# Revolution.net
KiCad netlist of a schematic drawn in Altium Designer
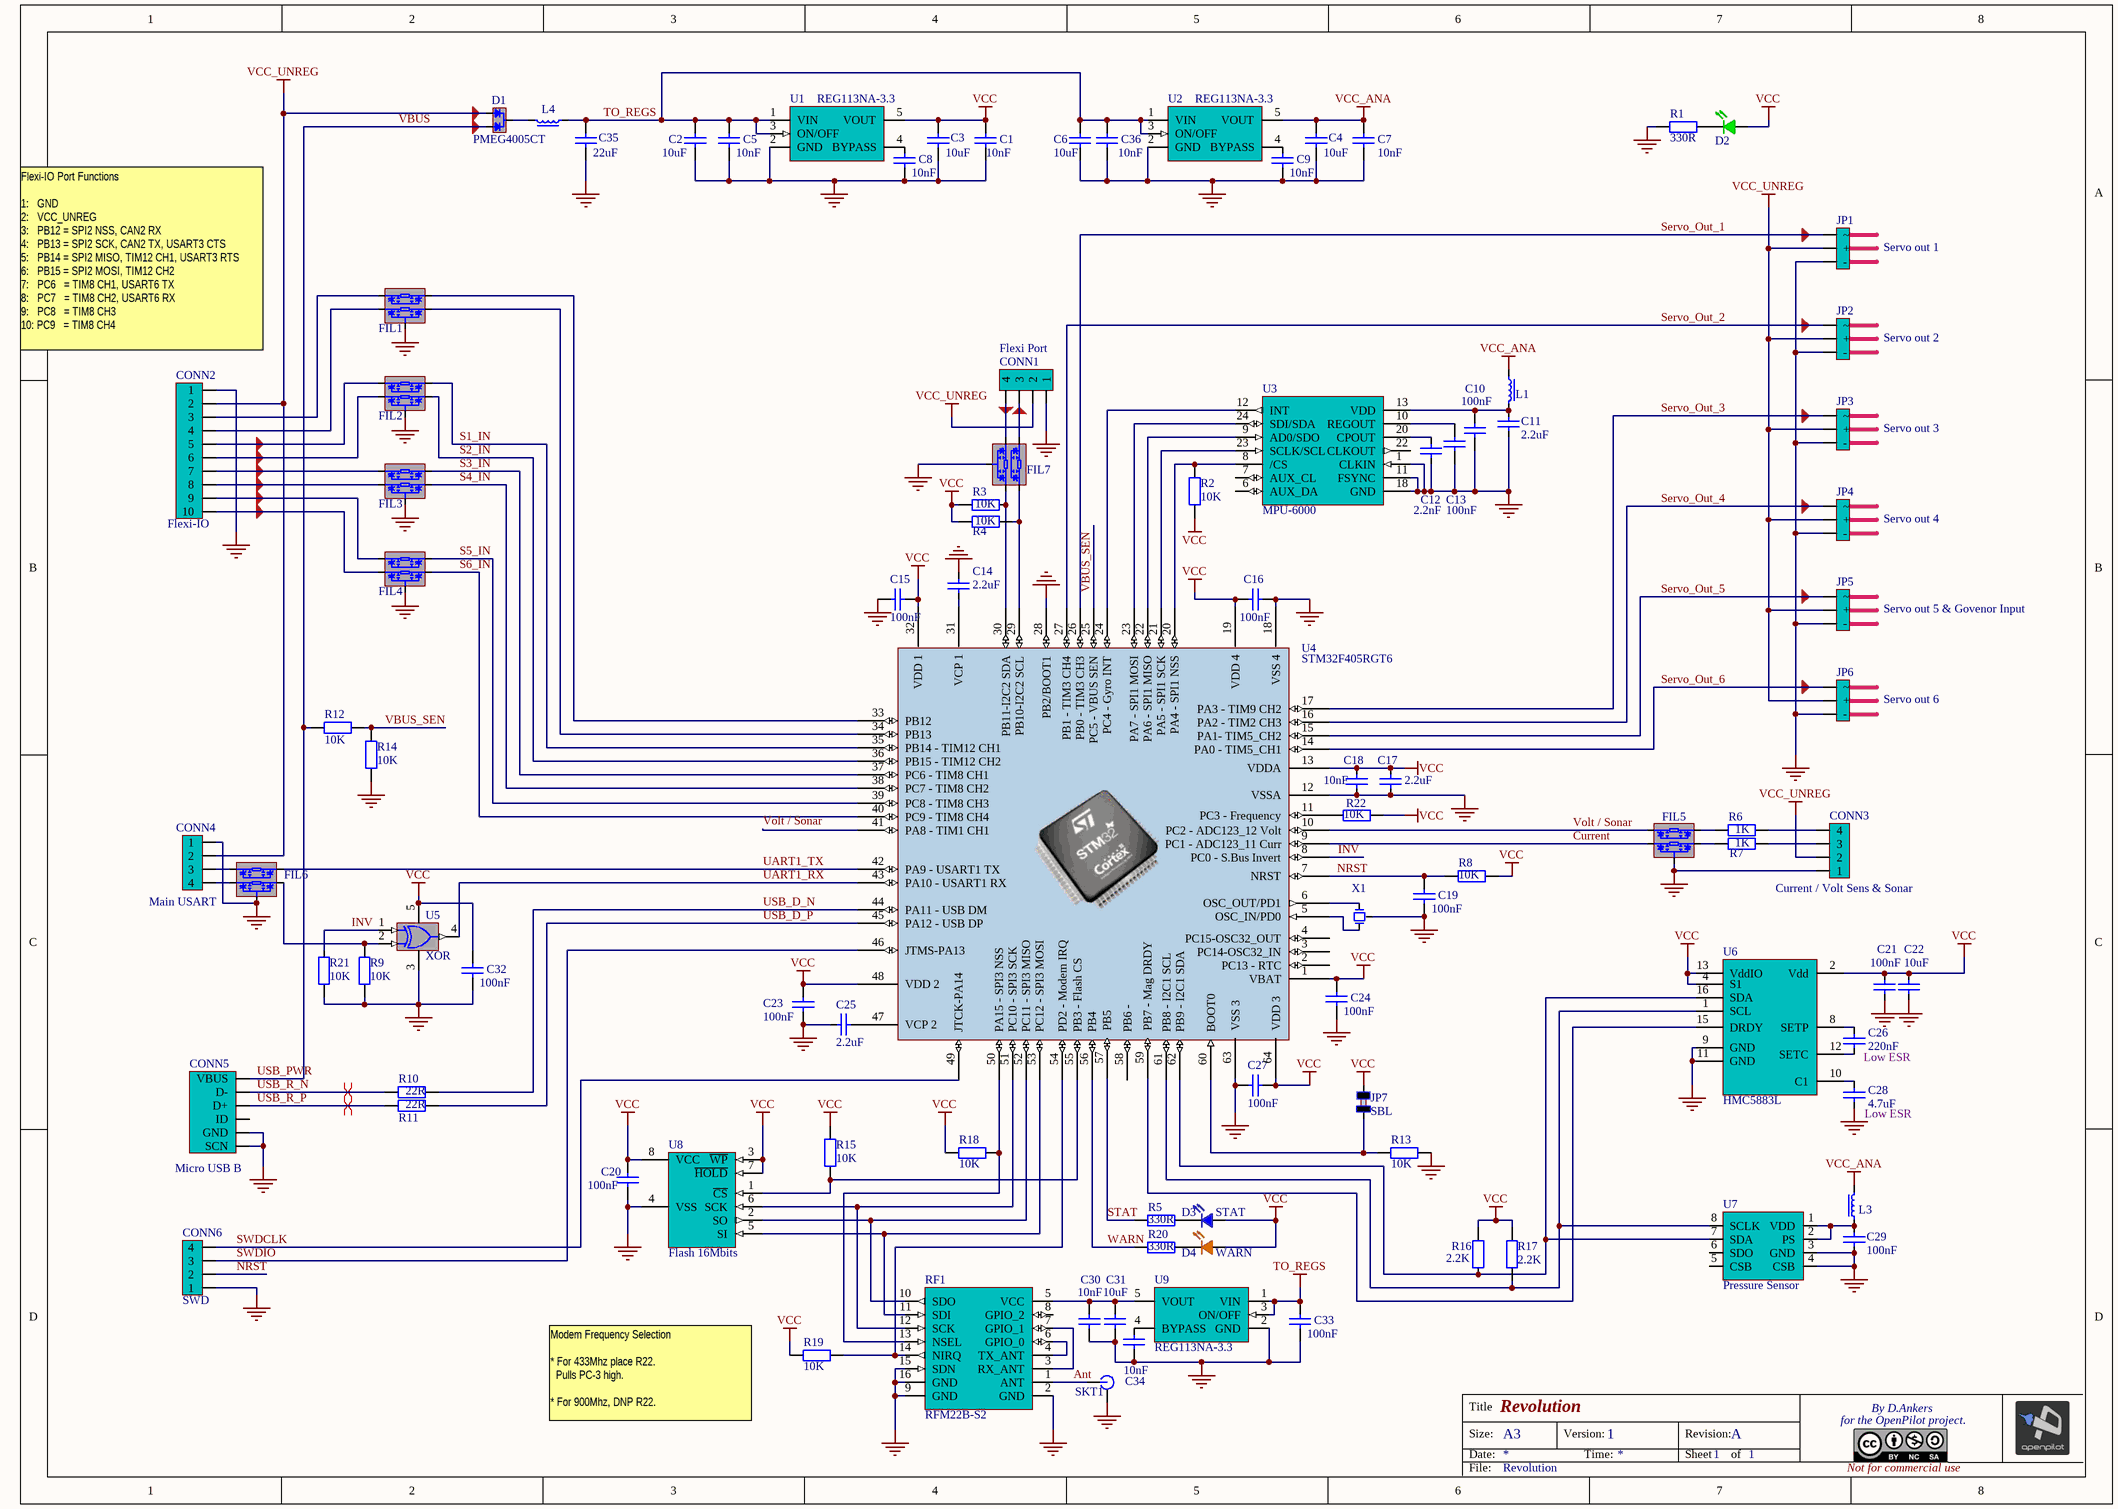
[diagram p0: Revolution.SchDoc]

(export (version "E")
  (design (tool "Eeschema 10.0.6"))
  (components
    (comp (ref "C1")
      (value "10nF")
      (footprint "CAP402N")
      (description "Capacitor SMD")
      (fields (field (name "Comment") "10n") (field (name "PUBLISHER") "The OpenPilot Project"))
      (libsource (lib "") (part "Cap402_1"))
    )
    (comp (ref "C2")
      (value "10uF")
      (footprint "CAP805L")
      (description "Capacitor SMD")
      (fields (field (name "Comment") "Cap805") (field (name "PUBLISHER") "The OpenPilot Project"))
      (libsource (lib "OpenPilot") (part "Cap805"))
    )
    (comp (ref "C3")
      (value "10uF")
      (footprint "CAP805L")
      (description "Capacitor SMD")
      (fields (field (name "Comment") "Cap805") (field (name "PUBLISHER") "The OpenPilot Project"))
      (libsource (lib "OpenPilot") (part "Cap805"))
    )
    (comp (ref "C4")
      (value "10uF")
      (footprint "CAP805L")
      (description "Capacitor SMD")
      (fields (field (name "Comment") "Cap805") (field (name "PUBLISHER") "The OpenPilot Project"))
      (libsource (lib "OpenPilot") (part "Cap805"))
    )
    (comp (ref "C5")
      (value "10nF")
      (footprint "CAP402N")
      (description "Capacitor SMD")
      (fields (field (name "Comment") "10n") (field (name "PUBLISHER") "The OpenPilot Project"))
      (libsource (lib "") (part "Cap402_1"))
    )
    (comp (ref "C6")
      (value "10uF")
      (footprint "CAP805L")
      (description "Capacitor SMD")
      (fields (field (name "Comment") "Cap805") (field (name "PUBLISHER") "The OpenPilot Project"))
      (libsource (lib "OpenPilot") (part "Cap805"))
    )
    (comp (ref "C7")
      (value "10nF")
      (footprint "CAP402N")
      (description "Capacitor SMD")
      (fields (field (name "Comment") "10n") (field (name "PUBLISHER") "The OpenPilot Project"))
      (libsource (lib "") (part "Cap402_1"))
    )
    (comp (ref "C8")
      (value "10nF")
      (footprint "CAP402N")
      (description "Capacitor SMD")
      (fields (field (name "Comment") "10n") (field (name "PUBLISHER") "The OpenPilot Project"))
      (libsource (lib "") (part "Cap402_2"))
    )
    (comp (ref "C9")
      (value "10nF")
      (footprint "CAP402N")
      (description "Capacitor SMD")
      (fields (field (name "Comment") "10n") (field (name "PUBLISHER") "The OpenPilot Project"))
      (libsource (lib "") (part "Cap402_2"))
    )
    (comp (ref "C10")
      (value "100nF")
      (footprint "CAP402N")
      (description "Capacitor SMD")
      (fields (field (name "Comment") "Cap402") (field (name "PUBLISHER") "The OpenPilot Project"))
      (libsource (lib "") (part "Cap402_1"))
    )
    (comp (ref "C11")
      (value "2.2uF")
      (footprint "CAP603L")
      (description "Capacitor SMD")
      (fields (field (name "Comment") "Cap603") (field (name "PUBLISHER") "The OpenPilot Project"))
      (libsource (lib "OpenPilot") (part "Cap603"))
    )
    (comp (ref "C12")
      (value "2.2nF")
      (footprint "CAP603L")
      (description "Capacitor SMD")
      (fields (field (name "Comment") "Cap603") (field (name "PUBLISHER") "The OpenPilot Project"))
      (libsource (lib "OpenPilot") (part "Cap603"))
    )
    (comp (ref "C13")
      (value "100nF")
      (footprint "CAP402N")
      (description "Capacitor SMD")
      (fields (field (name "Comment") "Cap402") (field (name "PUBLISHER") "The OpenPilot Project"))
      (libsource (lib "") (part "Cap402_1"))
    )
    (comp (ref "C14")
      (value "2.2uF")
      (footprint "CAP603L")
      (description "Capacitor SMD")
      (fields (field (name "Comment") "Cap603") (field (name "PUBLISHER") "The OpenPilot Project"))
      (libsource (lib "OpenPilot") (part "Cap603"))
    )
    (comp (ref "C15")
      (value "100nF")
      (footprint "CAP402N")
      (description "Capacitor SMD")
      (fields (field (name "Comment") "Cap402") (field (name "PUBLISHER") "The OpenPilot Project"))
      (libsource (lib "") (part "Cap402_1"))
    )
    (comp (ref "C16")
      (value "100nF")
      (footprint "CAP402N")
      (description "Capacitor SMD")
      (fields (field (name "Comment") "Cap402") (field (name "PUBLISHER") "The OpenPilot Project"))
      (libsource (lib "") (part "Cap402_1"))
    )
    (comp (ref "C17")
      (value "2.2uF")
      (footprint "CAP603L")
      (description "Capacitor SMD")
      (fields (field (name "Comment") "Cap603") (field (name "PUBLISHER") "The OpenPilot Project"))
      (libsource (lib "OpenPilot") (part "Cap603"))
    )
    (comp (ref "C18")
      (value "10nF")
      (footprint "CAP402N")
      (description "Capacitor SMD")
      (fields (field (name "Comment") "10n") (field (name "PUBLISHER") "The OpenPilot Project"))
      (libsource (lib "OpenPilot") (part "Cap402"))
    )
    (comp (ref "C19")
      (value "100nF")
      (footprint "CAP402N")
      (description "Capacitor SMD")
      (fields (field (name "Comment") "Cap402") (field (name "PUBLISHER") "The OpenPilot Project"))
      (libsource (lib "") (part "Cap402_1"))
    )
    (comp (ref "C20")
      (value "100nF")
      (footprint "CAP402N")
      (description "Capacitor SMD")
      (fields (field (name "Comment") "Cap402") (field (name "PUBLISHER") "The OpenPilot Project"))
      (libsource (lib "") (part "Cap402_1"))
    )
    (comp (ref "C21")
      (value "100nF")
      (footprint "CAP402N")
      (description "Capacitor SMD")
      (fields (field (name "Comment") "Cap402") (field (name "PUBLISHER") "The OpenPilot Project"))
      (libsource (lib "OpenPilot") (part "Cap402"))
    )
    (comp (ref "C22")
      (value "10uF")
      (footprint "CAP805L")
      (description "Capacitor SMD")
      (fields (field (name "Comment") "Cap805") (field (name "PUBLISHER") "The OpenPilot Project"))
      (libsource (lib "") (part "Cap805_1"))
    )
    (comp (ref "C23")
      (value "100nF")
      (footprint "CAP402N")
      (description "Capacitor SMD")
      (fields (field (name "Comment") "Cap402") (field (name "PUBLISHER") "The OpenPilot Project"))
      (libsource (lib "") (part "Cap402_1"))
    )
    (comp (ref "C24")
      (value "100nF")
      (footprint "CAP402N")
      (description "Capacitor SMD")
      (fields (field (name "Comment") "Cap402") (field (name "PUBLISHER") "The OpenPilot Project"))
      (libsource (lib "") (part "Cap402_1"))
    )
    (comp (ref "C25")
      (value "2.2uF")
      (footprint "CAP603L")
      (description "Capacitor SMD")
      (fields (field (name "Comment") "Cap603") (field (name "PUBLISHER") "The OpenPilot Project"))
      (libsource (lib "OpenPilot") (part "Cap603"))
    )
    (comp (ref "C26")
      (value "220nF")
      (footprint "CAP603L")
      (description "Capacitor SMD")
      (fields (field (name "Comment") "Cap603") (field (name "PUBLISHER") "The OpenPilot Project"))
      (libsource (lib "OpenPilot") (part "Cap603"))
    )
    (comp (ref "C27")
      (value "100nF")
      (footprint "CAP402N")
      (description "Capacitor SMD")
      (fields (field (name "Comment") "Cap402") (field (name "PUBLISHER") "The OpenPilot Project"))
      (libsource (lib "") (part "Cap402_1"))
    )
    (comp (ref "C28")
      (value "4.7uF")
      (footprint "CAP603L")
      (description "Capacitor SMD")
      (fields (field (name "Comment") "Cap603") (field (name "PUBLISHER") "The OpenPilot Project"))
      (libsource (lib "OpenPilot") (part "Cap603"))
    )
    (comp (ref "C29")
      (value "100nF")
      (footprint "CAP402N")
      (description "Capacitor SMD")
      (fields (field (name "Comment") "Cap402") (field (name "PUBLISHER") "The OpenPilot Project"))
      (libsource (lib "OpenPilot") (part "Cap402"))
    )
    (comp (ref "C30")
      (value "10nF")
      (footprint "CAP402N")
      (description "Capacitor SMD")
      (fields (field (name "Comment") "10n") (field (name "PUBLISHER") "The OpenPilot Project"))
      (libsource (lib "") (part "Cap402_1"))
    )
    (comp (ref "C31")
      (value "10uF")
      (footprint "CAP805L")
      (description "Capacitor SMD")
      (fields (field (name "Comment") "Cap805") (field (name "PUBLISHER") "The OpenPilot Project"))
      (libsource (lib "OpenPilot") (part "Cap805"))
    )
    (comp (ref "C32")
      (value "100nF")
      (footprint "CAP402N")
      (description "Capacitor SMD")
      (fields (field (name "Comment") "Cap402") (field (name "PUBLISHER") "The OpenPilot Project"))
      (libsource (lib "") (part "Cap402_1"))
    )
    (comp (ref "C33")
      (value "100nF")
      (footprint "CAP402N")
      (description "Capacitor SMD")
      (fields (field (name "Comment") "Cap402") (field (name "PUBLISHER") "The OpenPilot Project"))
      (libsource (lib "") (part "Cap402_1"))
    )
    (comp (ref "C34")
      (value "10nF")
      (footprint "CAP402N")
      (description "Capacitor SMD")
      (fields (field (name "Comment") "10n") (field (name "PUBLISHER") "The OpenPilot Project"))
      (libsource (lib "") (part "Cap402_2"))
    )
    (comp (ref "C35")
      (value "22uF")
      (footprint "CAP805L")
      (description "Capacitor SMD")
      (fields (field (name "Comment") "Cap805") (field (name "PUBLISHER") "The OpenPilot Project"))
      (libsource (lib "OpenPilot") (part "Cap805"))
    )
    (comp (ref "C36")
      (value "10nF")
      (footprint "CAP402N")
      (description "Capacitor SMD")
      (fields (field (name "Comment") "10n") (field (name "PUBLISHER") "The OpenPilot Project"))
      (libsource (lib "") (part "Cap402_1"))
    )
    (comp (ref "CONN1")
      (value "Flexi Port")
      (footprint "JST SH 4 Pin Side Entry")
      (description "JST-SH 4-pin Side Entry Socket")
      (fields (field (name "MANUFACTURER") "Generic Components"))
      (libsource (lib "OpenPilot") (part "JST-SH 4-pin Side Entry Socket"))
    )
    (comp (ref "CONN2")
      (value "Flexi-IO")
      (footprint "JST SH 10 PIN SIDE ENTRY")
      (description "JST-SH 10-pin Side Entry Socket")
      (fields (field (name "MANUFACTURER") "Generic Components"))
      (libsource (lib "OpenPilot") (part "JST-SH 10-pin Side Entry Socket"))
    )
    (comp (ref "CONN3")
      (value "Current / Volt Sens & Sonar")
      (footprint "JST SH 4 Pin Side Entry")
      (description "JST-SH 4-pin Side Entry Socket")
      (fields (field (name "MANUFACTURER") "Generic Components"))
      (libsource (lib "") (part "JST-SH 4-pin Side Entry Socket_3"))
    )
    (comp (ref "CONN4")
      (value "Main USART")
      (footprint "JST SH 4 Pin Side Entry")
      (description "JST-SH 4-pin Side Entry Socket")
      (fields (field (name "MANUFACTURER") "Generic Components"))
      (libsource (lib "") (part "JST-SH 4-pin Side Entry Socket_2"))
    )
    (comp (ref "CONN5")
      (value "Micro USB B")
      (footprint "Micro_USB")
      (description "USB Micro B SMT Socket")
      (fields (field (name "PUBLISHER") "The OpenPilot Project"))
      (libsource (lib "OpenPilot") (part "USB Micro B SMT"))
    )
    (comp (ref "CONN6")
      (value "SWD")
      (footprint "JST SH 4 Pin Side Entry")
      (description "JST-SH 4-pin Side Entry Socket")
      (fields (field (name "MANUFACTURER") "Generic Components"))
      (libsource (lib "") (part "JST-SH 4-pin Side Entry Socket_1"))
    )
    (comp (ref "D1")
      (value "PMEG4005CT")
      (footprint "SOT23-3N")
      (description "Dual Diode Command Cathode 500ma")
      (fields (field (name "PUBLISHER") "The OpenPilot Project"))
      (libsource (lib "OpenPilot") (part "PMEG4005CT"))
    )
    (comp (ref "D2")
      (value "Green")
      (footprint "LED603N")
      (description "Green 603 LED")
      (libsource (lib "OpenPilot") (part "LED 603 Gr"))
    )
    (comp (ref "D3")
      (value "STAT")
      (footprint "LED603N")
      (description "Blue 603 LED")
      (libsource (lib "OpenPilot") (part "LED 603 Bl"))
    )
    (comp (ref "D4")
      (value "WARN")
      (footprint "LED603N")
      (description "Orange 603 LED")
      (libsource (lib "OpenPilot") (part "LED 603 Or"))
    )
    (comp (ref "FIL1")
      (value "IP4256CZ5-W,115")
      (footprint "SOT-665")
      (description "IP4256CZ5-W,115 2 channel, 100R, 30pF, RF ESD Filter")
      (fields
        (field (name "MANUFACTURER") "Generic Components")
        (field (name "PUBLISHER") "The OpenPilot Project")
      )
      (libsource (lib "OpenPilot") (part "RF Filter 100R 30pF"))
    )
    (comp (ref "FIL2")
      (value "IP4256CZ5-W,115")
      (footprint "SOT-665")
      (description "IP4256CZ5-W,115 2 channel, 100R, 30pF, RF ESD Filter")
      (fields
        (field (name "MANUFACTURER") "Generic Components")
        (field (name "PUBLISHER") "The OpenPilot Project")
      )
      (libsource (lib "OpenPilot") (part "RF Filter 100R 30pF"))
    )
    (comp (ref "FIL3")
      (value "IP4256CZ5-W,115")
      (footprint "SOT-665")
      (description "IP4256CZ5-W,115 2 channel, 100R, 30pF, RF ESD Filter")
      (fields
        (field (name "MANUFACTURER") "Generic Components")
        (field (name "PUBLISHER") "The OpenPilot Project")
      )
      (libsource (lib "OpenPilot") (part "RF Filter 100R 30pF"))
    )
    (comp (ref "FIL4")
      (value "IP4256CZ5-W,115")
      (footprint "SOT-665")
      (description "IP4256CZ5-W,115 2 channel, 100R, 30pF, RF ESD Filter")
      (fields
        (field (name "MANUFACTURER") "Generic Components")
        (field (name "PUBLISHER") "The OpenPilot Project")
      )
      (libsource (lib "OpenPilot") (part "RF Filter 100R 30pF"))
    )
    (comp (ref "FIL5")
      (value "IP4256CZ5-W,115")
      (footprint "SOT-665")
      (description "IP4256CZ5-W,115 2 channel, 100R, 30pF, RF ESD Filter")
      (fields
        (field (name "MANUFACTURER") "Generic Components")
        (field (name "PUBLISHER") "The OpenPilot Project")
      )
      (libsource (lib "OpenPilot") (part "RF Filter 100R 30pF"))
    )
    (comp (ref "FIL6")
      (value "IP4256CZ5-W,115")
      (footprint "SOT-665")
      (description "IP4256CZ5-W,115 2 channel, 100R, 30pF, RF ESD Filter")
      (fields
        (field (name "MANUFACTURER") "Generic Components")
        (field (name "PUBLISHER") "The OpenPilot Project")
      )
      (libsource (lib "OpenPilot") (part "RF Filter 100R 30pF"))
    )
    (comp (ref "FIL7")
      (value "IP4256CZ5-W,115")
      (footprint "SOT-665")
      (description "IP4256CZ5-W,115 2 channel, 100R, 30pF, RF ESD Filter")
      (fields
        (field (name "MANUFACTURER") "Generic Components")
        (field (name "PUBLISHER") "The OpenPilot Project")
      )
      (libsource (lib "OpenPilot") (part "RF Filter 100R 30pF"))
    )
    (comp (ref "JP1")
      (value "Servo out 1")
      (footprint "SIP3 - 0.1")
      (description "Header, 3-Pin, 0.1\"")
      (fields (field (name "MANUFACTURER") "Generic Components"))
      (libsource (lib "OpenPilot") (part "Hdr 3 Pin 0.1"))
    )
    (comp (ref "JP2")
      (value "Servo out 2")
      (footprint "SIP3 - 0.1")
      (description "Header, 3-Pin, 0.1\"")
      (fields (field (name "MANUFACTURER") "Generic Components"))
      (libsource (lib "OpenPilot") (part "Hdr 3 Pin 0.1"))
    )
    (comp (ref "JP3")
      (value "Servo out 3")
      (footprint "SIP3 - 0.1")
      (description "Header, 3-Pin, 0.1\"")
      (fields (field (name "MANUFACTURER") "Generic Components"))
      (libsource (lib "OpenPilot") (part "Hdr 3 Pin 0.1"))
    )
    (comp (ref "JP4")
      (value "Servo out 4")
      (footprint "SIP3 - 0.1")
      (description "Header, 3-Pin, 0.1\"")
      (fields (field (name "MANUFACTURER") "Generic Components"))
      (libsource (lib "OpenPilot") (part "Hdr 3 Pin 0.1"))
    )
    (comp (ref "JP5")
      (value "Servo out 5 & Govenor Input")
      (footprint "SIP3 - 0.1")
      (description "Header, 3-Pin, 0.1\"")
      (fields (field (name "MANUFACTURER") "Generic Components"))
      (libsource (lib "OpenPilot") (part "Hdr 3 Pin 0.1"))
    )
    (comp (ref "JP6")
      (value "Servo out 6")
      (footprint "SIP3 - 0.1")
      (description "Header, 3-Pin, 0.1\"")
      (fields (field (name "MANUFACTURER") "Generic Components"))
      (libsource (lib "OpenPilot") (part "Hdr 3 Pin 0.1"))
    )
    (comp (ref "JP7")
      (value "SBL")
      (footprint "TOUCH JMP 2PAD")
      (description "2 Pad Touch Jumper")
      (fields (field (name "PUBLISHER") "The OpenPilot Project"))
      (libsource (lib "OpenPilot") (part "2 PAD Touch JMP"))
    )
    (comp (ref "L1")
      (value "FB 300mA")
      (footprint "IND603N")
      (description "Ferrite Bead 300mA")
      (fields
        (field (name "MANUFACTURER") "Generic Components")
        (field (name "PUBLISHER") "The OpenPilot Project")
      )
      (libsource (lib "OpenPilot") (part "FerriteBead 300mA"))
    )
    (comp (ref "L3")
      (value "FB 300mA")
      (footprint "IND603N")
      (description "Ferrite Bead 300mA")
      (fields
        (field (name "MANUFACTURER") "Generic Components")
        (field (name "PUBLISHER") "The OpenPilot Project")
      )
      (libsource (lib "OpenPilot") (part "FerriteBead 300mA"))
    )
    (comp (ref "L4")
      (value "FB 300mA")
      (footprint "IND603N")
      (description "Ferrite Bead 300mA")
      (fields
        (field (name "MANUFACTURER") "Generic Components")
        (field (name "PUBLISHER") "The OpenPilot Project")
      )
      (libsource (lib "OpenPilot") (part "FerriteBead 300mA"))
    )
    (comp (ref "R1")
      (value "330R")
      (footprint "RES402N")
      (description "Resistor SMD")
      (fields (field (name "Comment") "Res402") (field (name "PUBLISHER") "The OpenPilot Project"))
      (libsource (lib "") (part "Res402_1"))
    )
    (comp (ref "R2")
      (value "10K")
      (footprint "RES402N")
      (description "Resistor SMD")
      (fields (field (name "Comment") "Res402") (field (name "PUBLISHER") "The OpenPilot Project"))
      (libsource (lib "") (part "Res402_3"))
    )
    (comp (ref "R3")
      (value "10K")
      (footprint "RES402N")
      (description "Resistor SMD")
      (fields (field (name "Comment") "Res402") (field (name "PUBLISHER") "The OpenPilot Project"))
      (libsource (lib "") (part "Res402_6"))
    )
    (comp (ref "R4")
      (value "10K")
      (footprint "RES402N")
      (description "Resistor SMD")
      (fields (field (name "Comment") "Res402") (field (name "PUBLISHER") "The OpenPilot Project"))
      (libsource (lib "OpenPilot") (part "Res402"))
    )
    (comp (ref "R5")
      (value "330R")
      (footprint "RES402N")
      (description "Resistor SMD")
      (fields (field (name "Comment") "Res402") (field (name "PUBLISHER") "The OpenPilot Project"))
      (libsource (lib "OpenPilot") (part "Res402"))
    )
    (comp (ref "R6")
      (value "1K")
      (footprint "RES402N")
      (description "Resistor SMD")
      (fields (field (name "Comment") "Res402") (field (name "PUBLISHER") "The OpenPilot Project"))
      (libsource (lib "") (part "Res402_1"))
    )
    (comp (ref "R7")
      (value "1K")
      (footprint "RES402N")
      (description "Resistor SMD")
      (fields (field (name "Comment") "Res402") (field (name "PUBLISHER") "The OpenPilot Project"))
      (libsource (lib "") (part "Res402_1"))
    )
    (comp (ref "R8")
      (value "10K")
      (footprint "RES402N")
      (description "Resistor SMD")
      (fields (field (name "Comment") "Res402") (field (name "PUBLISHER") "The OpenPilot Project"))
      (libsource (lib "") (part "Res402_1"))
    )
    (comp (ref "R9")
      (value "10K")
      (footprint "RES402N")
      (description "Resistor SMD")
      (fields (field (name "Comment") "Res402") (field (name "PUBLISHER") "The OpenPilot Project"))
      (libsource (lib "") (part "Res402_3"))
    )
    (comp (ref "R10")
      (value "22R")
      (footprint "RES402N")
      (description "Resistor SMD")
      (fields (field (name "Comment") "Res402") (field (name "PUBLISHER") "The OpenPilot Project"))
      (libsource (lib "OpenPilot") (part "Res402"))
    )
    (comp (ref "R11")
      (value "22R")
      (footprint "RES402N")
      (description "Resistor SMD")
      (fields (field (name "Comment") "Res402") (field (name "PUBLISHER") "The OpenPilot Project"))
      (libsource (lib "OpenPilot") (part "Res402"))
    )
    (comp (ref "R12")
      (value "10K")
      (footprint "RES402N")
      (description "Resistor SMD")
      (fields (field (name "Comment") "Res402") (field (name "PUBLISHER") "The OpenPilot Project"))
      (libsource (lib "") (part "Res402_1"))
    )
    (comp (ref "R13")
      (value "10K")
      (footprint "RES402N")
      (description "Resistor SMD")
      (fields (field (name "Comment") "Res402") (field (name "PUBLISHER") "The OpenPilot Project"))
      (libsource (lib "") (part "Res402_1"))
    )
    (comp (ref "R14")
      (value "10K")
      (footprint "RES402N")
      (description "Resistor SMD")
      (fields (field (name "Comment") "Res402") (field (name "PUBLISHER") "The OpenPilot Project"))
      (libsource (lib "") (part "Res402_3"))
    )
    (comp (ref "R15")
      (value "10K")
      (footprint "RES402N")
      (description "Resistor SMD")
      (fields (field (name "Comment") "Res402") (field (name "PUBLISHER") "The OpenPilot Project"))
      (libsource (lib "") (part "Res402_5"))
    )
    (comp (ref "R16")
      (value "2.2K")
      (footprint "RES402N")
      (description "Resistor SMD")
      (fields (field (name "Comment") "Res402") (field (name "PUBLISHER") "The OpenPilot Project"))
      (libsource (lib "") (part "Res402_4"))
    )
    (comp (ref "R17")
      (value "2.2K")
      (footprint "RES402N")
      (description "Resistor SMD")
      (fields (field (name "Comment") "Res402") (field (name "PUBLISHER") "The OpenPilot Project"))
      (libsource (lib "") (part "Res402_5"))
    )
    (comp (ref "R18")
      (value "10K")
      (footprint "RES402N")
      (description "Resistor SMD")
      (fields (field (name "Comment") "Res402") (field (name "PUBLISHER") "The OpenPilot Project"))
      (libsource (lib "") (part "Res402_1"))
    )
    (comp (ref "R19")
      (value "10K")
      (footprint "RES402N")
      (description "Resistor SMD")
      (fields (field (name "Comment") "Res402") (field (name "PUBLISHER") "The OpenPilot Project"))
      (libsource (lib "OpenPilot") (part "Res402"))
    )
    (comp (ref "R20")
      (value "330R")
      (footprint "RES402N")
      (description "Resistor SMD")
      (fields (field (name "Comment") "Res402") (field (name "PUBLISHER") "The OpenPilot Project"))
      (libsource (lib "OpenPilot") (part "Res402"))
    )
    (comp (ref "R21")
      (value "10K")
      (footprint "RES402N")
      (description "Resistor SMD")
      (fields (field (name "Comment") "Res402") (field (name "PUBLISHER") "The OpenPilot Project"))
      (libsource (lib "") (part "Res402_2"))
    )
    (comp (ref "R22")
      (value "10K")
      (footprint "RES402N")
      (description "Resistor SMD")
      (fields (field (name "Comment") "Res402") (field (name "PUBLISHER") "The OpenPilot Project"))
      (libsource (lib "OpenPilot") (part "Res402"))
    )
    (comp (ref "RF1")
      (value "RFM22B-S2")
      (footprint "RFM22-S2")
      (description "UHF 100mW Transceiver")
      (libsource (lib "OpenPilot") (part "RFM22B-S2"))
    )
    (comp (ref "SKT1")
      (value "MMCX Thru hole")
      (footprint "MMCX_SOCKET")
      (description "MMCX Socket")
      (libsource (lib "OpenPilot") (part "MMCX Thru hole"))
    )
    (comp (ref "U1")
      (value "REG113NA-3.3")
      (footprint "SOT23-5L")
      (description "3.3V 400mA LDO Regulator")
      (libsource (lib "OpenPilot") (part "REG113NA-3.3"))
    )
    (comp (ref "U2")
      (value "REG113NA-3.3")
      (footprint "SOT23-5L")
      (description "3.3V 400mA LDO Regulator")
      (libsource (lib "OpenPilot") (part "REG113NA-3.3"))
    )
    (comp (ref "U3")
      (value "MPU-6000")
      (footprint "IMU-3000")
      (description "Invensense MPU-3/6000,  3-axis Gyros & Accel on 6000")
      (fields (field (name "MANUFACTURER") "Invensense") (field (name "PUBLISHER") "The OpenPilot Project"))
      (libsource (lib "OpenPilot") (part "MPU-3/6000"))
    )
    (comp (ref "U4")
      (value "STM32F405RGT6")
      (footprint "STM32 64 Lead")
      (description "STM32 ARM-based 32-bit MCU with 1MB Flash, 64-pin LQFP, Industrial Temperature")
      (libsource (lib "OpenPilot") (part "STM32F103RET6"))
    )
    (comp (ref "U5")
      (value "XOR")
      (footprint "DCK-5")
      (description "XOR Gate SN74LVC1G86DCKR")
      (libsource (lib "OpenPilot") (part "XOR SN74LVC1G86DCKR"))
    )
    (comp (ref "U6")
      (value "HMC5883L")
      (footprint "LPCC-16")
      (description "IC, Magnetometer, 3 axis, +/- 8 Oe, I2C, 160Hz")
      (fields (field (name "MANUFACTURER") "Honeywell") (field (name "PUBLISHER") "The OpenPilot Project"))
      (libsource (lib "OpenPilot") (part "HMC5883L"))
    )
    (comp (ref "U7")
      (value "Pressure Sensor")
      (footprint "MS5611-01BA03")
      (description "Pressure Sensor - MS5611-01BA03")
      (libsource (lib "OpenPilot") (part "MS5611-01BA03"))
    )
    (comp (ref "U8")
      (value "Flash 16Mbits")
      (footprint "SOIC8_N")
      (description "16Mbit SPI Flash Memory")
      (fields (field (name "PUBLISHER") "The OpenPilot Project"))
      (libsource (lib "OpenPilot") (part "Flash 16Mb 75MHZ 8SOIC"))
    )
    (comp (ref "U9")
      (value "REG113NA-3.3")
      (footprint "SOT23-5L")
      (description "3.3V 400mA LDO Regulator")
      (libsource (lib "") (part "REG113NA-3.3_1"))
    )
    (comp (ref "X1")
      (value "8Mhz Ceralock")
      (footprint "CERALOCK 8Mhz")
      (description "Ceralock 8Mhz with caps")
      (fields (field (name "PUBLISHER") "The OpenPilot Project"))
      (libsource (lib "OpenPilot") (part "CERALOCK8"))
    )
  )
  (nets
    (net (code "1") (name "/Ant") (class "Default")
      (node (ref "RF1") (pin "1") (pinfunction "ANT_1") (pintype "passive"))
      (node (ref "SKT1") (pin "1") (pinfunction "PIN_1") (pintype "passive"))
    )
    (net (code "2") (name "/Current") (class "Default")
      (node (ref "FIL5") (pin "1") (pinfunction "1_1") (pintype "passive"))
      (node (ref "U4") (pin "9") (pinfunction "PC1_-_ADC123_11_Curr_9") (pintype "bidirectional"))
    )
    (net (code "3") (name "/INV") (class "Default")
      (node (ref "R21") (pin "2") (pinfunction "2_2") (pintype "passive"))
      (node (ref "U4") (pin "8") (pinfunction "PC0_-_S.Bus_Invert_8") (pintype "bidirectional"))
      (node (ref "U5") (pin "1") (pinfunction "A_1") (pintype "input"))
    )
    (net (code "4") (name "/NRST") (class "Default")
      (node (ref "C19") (pin "2") (pinfunction "2_2") (pintype "passive"))
      (node (ref "CONN6") (pin "2") (pinfunction "2_2") (pintype "passive"))
      (node (ref "R8") (pin "1") (pinfunction "1_1") (pintype "passive"))
      (node (ref "U4") (pin "7") (pinfunction "NRST_7") (pintype "bidirectional"))
    )
    (net (code "5") (name "/S1_IN") (class "Default")
      (node (ref "FIL2") (pin "3") (pinfunction "3_3") (pintype "passive"))
      (node (ref "U4") (pin "35") (pinfunction "PB14_-_TIM12_CH1_35") (pintype "bidirectional"))
    )
    (net (code "6") (name "/S2_IN") (class "Default")
      (node (ref "FIL2") (pin "1") (pinfunction "1_1") (pintype "passive"))
      (node (ref "U4") (pin "36") (pinfunction "PB15_-_TIM12_CH2_36") (pintype "bidirectional"))
    )
    (net (code "7") (name "/S3_IN") (class "Default")
      (node (ref "FIL3") (pin "3") (pinfunction "3_3") (pintype "passive"))
      (node (ref "U4") (pin "37") (pinfunction "PC6_-_TIM8_CH1_37") (pintype "bidirectional"))
    )
    (net (code "8") (name "/S4_IN") (class "Default")
      (node (ref "FIL3") (pin "1") (pinfunction "1_1") (pintype "passive"))
      (node (ref "U4") (pin "38") (pinfunction "PC7_-_TIM8_CH2_38") (pintype "bidirectional"))
    )
    (net (code "9") (name "/S5_IN") (class "Default")
      (node (ref "FIL4") (pin "3") (pinfunction "3_3") (pintype "passive"))
      (node (ref "U4") (pin "39") (pinfunction "PC8_-_TIM8_CH3_39") (pintype "bidirectional"))
    )
    (net (code "10") (name "/S6_IN") (class "Default")
      (node (ref "FIL4") (pin "1") (pinfunction "1_1") (pintype "passive"))
      (node (ref "U4") (pin "40") (pinfunction "PC9_-_TIM8_CH4_40") (pintype "bidirectional"))
    )
    (net (code "11") (name "/STAT") (class "Default")
      (node (ref "R5") (pin "2") (pinfunction "2_2") (pintype "passive"))
      (node (ref "U4") (pin "57") (pinfunction "PB5_57") (pintype "bidirectional"))
    )
    (net (code "12") (name "/SWDCLK") (class "Default")
      (node (ref "CONN6") (pin "4") (pinfunction "4_4") (pintype "passive"))
      (node (ref "U4") (pin "49") (pinfunction "JTCK-PA14_49") (pintype "bidirectional"))
    )
    (net (code "13") (name "/SWDIO") (class "Default")
      (node (ref "CONN6") (pin "3") (pinfunction "3_3") (pintype "passive"))
      (node (ref "U4") (pin "46") (pinfunction "JTMS-PA13_46") (pintype "bidirectional"))
    )
    (net (code "14") (name "/Servo_Out_1") (class "Default")
      (node (ref "JP1") (pin "1") (pinfunction "~_1") (pintype "passive"))
      (node (ref "U4") (pin "26") (pinfunction "PB0_-_TIM3_CH3_26") (pintype "bidirectional"))
    )
    (net (code "15") (name "/Servo_Out_2") (class "Default")
      (node (ref "JP2") (pin "1") (pinfunction "~_1") (pintype "passive"))
      (node (ref "U4") (pin "27") (pinfunction "PB1_-_TIM3_CH4_27") (pintype "bidirectional"))
    )
    (net (code "16") (name "/Servo_Out_3") (class "Default")
      (node (ref "JP3") (pin "1") (pinfunction "~_1") (pintype "passive"))
      (node (ref "U4") (pin "17") (pinfunction "PA3_-_TIM9_CH2_17") (pintype "bidirectional"))
    )
    (net (code "17") (name "/Servo_Out_4") (class "Default")
      (node (ref "JP4") (pin "1") (pinfunction "~_1") (pintype "passive"))
      (node (ref "U4") (pin "16") (pinfunction "PA2_-_TIM2_CH3_16") (pintype "bidirectional"))
    )
    (net (code "18") (name "/Servo_Out_5") (class "Default")
      (node (ref "JP5") (pin "1") (pinfunction "~_1") (pintype "passive"))
      (node (ref "U4") (pin "15") (pinfunction "PA1-_TIM5_CH2_15") (pintype "bidirectional"))
    )
    (net (code "19") (name "/Servo_Out_6") (class "Default")
      (node (ref "JP6") (pin "1") (pinfunction "~_1") (pintype "passive"))
      (node (ref "U4") (pin "14") (pinfunction "PA0_-_TIM5_CH1_14") (pintype "bidirectional"))
    )
    (net (code "20") (name "/UART1_RX") (class "Default")
      (node (ref "U4") (pin "43") (pinfunction "PA10_-_USART1_RX_43") (pintype "bidirectional"))
      (node (ref "U5") (pin "4") (pinfunction "Y_4") (pintype "output"))
    )
    (net (code "21") (name "/UART1_TX") (class "Default")
      (node (ref "FIL6") (pin "3") (pinfunction "3_3") (pintype "passive"))
      (node (ref "U4") (pin "42") (pinfunction "PA9_-_USART1_TX_42") (pintype "bidirectional"))
    )
    (net (code "22") (name "/USB_D_N") (class "Default")
      (node (ref "R10") (pin "1") (pinfunction "1_1") (pintype "passive"))
      (node (ref "U4") (pin "44") (pinfunction "PA11_-_USB_DM_44") (pintype "bidirectional"))
    )
    (net (code "23") (name "/USB_D_P") (class "Default")
      (node (ref "R11") (pin "1") (pinfunction "1_1") (pintype "passive"))
      (node (ref "U4") (pin "45") (pinfunction "PA12_-_USB_DP_45") (pintype "bidirectional"))
    )
    (net (code "24") (name "/USB_PWR") (class "Default")
      (node (ref "CONN5") (pin "1") (pinfunction "VBUS_1") (pintype "passive"))
      (node (ref "D1") (pin "1") (pinfunction "A1_1") (pintype "passive"))
      (node (ref "R12") (pin "1") (pinfunction "1_1") (pintype "passive"))
    )
    (net (code "25") (name "/USB_R_N") (class "Default")
      (node (ref "CONN5") (pin "2") (pinfunction "D-_2") (pintype "passive"))
      (node (ref "R10") (pin "2") (pinfunction "2_2") (pintype "passive"))
    )
    (net (code "26") (name "/USB_R_P") (class "Default")
      (node (ref "CONN5") (pin "3") (pinfunction "D+_3") (pintype "passive"))
      (node (ref "R11") (pin "2") (pinfunction "2_2") (pintype "passive"))
    )
    (net (code "27") (name "/VBUS_SEN") (class "Default")
      (node (ref "R12") (pin "2") (pinfunction "2_2") (pintype "passive"))
      (node (ref "R14") (pin "2") (pinfunction "2_2") (pintype "passive"))
      (node (ref "U4") (pin "25") (pinfunction "PC5_-_VBUS_SEN_25") (pintype "bidirectional"))
    )
    (net (code "28") (name "/Volt {slash} Sonar") (class "Default")
      (node (ref "FIL5") (pin "3") (pinfunction "3_3") (pintype "passive"))
      (node (ref "U4") (pin "10") (pinfunction "PC2_-_ADC123_12_Volt_10") (pintype "bidirectional"))
      (node (ref "U4") (pin "41") (pinfunction "PA8_-_TIM1_CH1_41") (pintype "bidirectional"))
    )
    (net (code "29") (name "/WARN") (class "Default")
      (node (ref "R20") (pin "2") (pinfunction "2_2") (pintype "passive"))
      (node (ref "U4") (pin "56") (pinfunction "PB4_56") (pintype "bidirectional"))
    )
    (net (code "30") (name "GND") (class "Default")
      (node (ref "C1") (pin "2") (pinfunction "2_2") (pintype "passive"))
      (node (ref "C10") (pin "1") (pinfunction "1_1") (pintype "passive"))
      (node (ref "C11") (pin "2") (pinfunction "2_2") (pintype "passive"))
      (node (ref "C12") (pin "1") (pinfunction "1_1") (pintype "passive"))
      (node (ref "C13") (pin "2") (pinfunction "2_2") (pintype "passive"))
      (node (ref "C14") (pin "1") (pinfunction "1_1") (pintype "passive"))
      (node (ref "C15") (pin "2") (pinfunction "2_2") (pintype "passive"))
      (node (ref "C16") (pin "1") (pinfunction "1_1") (pintype "passive"))
      (node (ref "C17") (pin "1") (pinfunction "1_1") (pintype "passive"))
      (node (ref "C18") (pin "2") (pinfunction "2_2") (pintype "passive"))
      (node (ref "C19") (pin "1") (pinfunction "1_1") (pintype "passive"))
      (node (ref "C2") (pin "2") (pinfunction "2_2") (pintype "passive"))
      (node (ref "C20") (pin "1") (pinfunction "1_1") (pintype "passive"))
      (node (ref "C21") (pin "2") (pinfunction "2_2") (pintype "passive"))
      (node (ref "C22") (pin "1") (pinfunction "1_1") (pintype "passive"))
      (node (ref "C23") (pin "2") (pinfunction "2_2") (pintype "passive"))
      (node (ref "C24") (pin "1") (pinfunction "1_1") (pintype "passive"))
      (node (ref "C25") (pin "1") (pinfunction "1_1") (pintype "passive"))
      (node (ref "C27") (pin "2") (pinfunction "2_2") (pintype "passive"))
      (node (ref "C28") (pin "2") (pinfunction "2_2") (pintype "passive"))
      (node (ref "C29") (pin "2") (pinfunction "2_2") (pintype "passive"))
      (node (ref "C3") (pin "2") (pinfunction "2_2") (pintype "passive"))
      (node (ref "C30") (pin "2") (pinfunction "2_2") (pintype "passive"))
      (node (ref "C31") (pin "2") (pinfunction "2_2") (pintype "passive"))
      (node (ref "C32") (pin "2") (pinfunction "2_2") (pintype "passive"))
      (node (ref "C33") (pin "1") (pinfunction "1_1") (pintype "passive"))
      (node (ref "C34") (pin "2") (pinfunction "2_2") (pintype "passive"))
      (node (ref "C35") (pin "2") (pinfunction "2_2") (pintype "passive"))
      (node (ref "C36") (pin "2") (pinfunction "2_2") (pintype "passive"))
      (node (ref "C4") (pin "2") (pinfunction "2_2") (pintype "passive"))
      (node (ref "C5") (pin "2") (pinfunction "2_2") (pintype "passive"))
      (node (ref "C6") (pin "2") (pinfunction "2_2") (pintype "passive"))
      (node (ref "C7") (pin "2") (pinfunction "2_2") (pintype "passive"))
      (node (ref "C8") (pin "2") (pinfunction "2_2") (pintype "passive"))
      (node (ref "C9") (pin "2") (pinfunction "2_2") (pintype "passive"))
      (node (ref "CONN1") (pin "1") (pinfunction "1_1") (pintype "passive"))
      (node (ref "CONN2") (pin "1") (pinfunction "1_1") (pintype "passive"))
      (node (ref "CONN3") (pin "1") (pinfunction "1_1") (pintype "passive"))
      (node (ref "CONN4") (pin "1") (pinfunction "1_1") (pintype "passive"))
      (node (ref "CONN5") (pin "0") (pinfunction "SCN_0") (pintype "passive"))
      (node (ref "CONN5") (pin "5") (pinfunction "GND_5") (pintype "passive"))
      (node (ref "CONN6") (pin "1") (pinfunction "1_1") (pintype "passive"))
      (node (ref "FIL1") (pin "2") (pinfunction "PAD_2") (pintype "passive"))
      (node (ref "FIL2") (pin "2") (pinfunction "PAD_2") (pintype "passive"))
      (node (ref "FIL3") (pin "2") (pinfunction "PAD_2") (pintype "passive"))
      (node (ref "FIL4") (pin "2") (pinfunction "PAD_2") (pintype "passive"))
      (node (ref "FIL5") (pin "2") (pinfunction "PAD_2") (pintype "passive"))
      (node (ref "FIL6") (pin "2") (pinfunction "PAD_2") (pintype "passive"))
      (node (ref "FIL7") (pin "2") (pinfunction "PAD_2") (pintype "passive"))
      (node (ref "JP1") (pin "3") (pinfunction "-_3") (pintype "passive"))
      (node (ref "JP2") (pin "3") (pinfunction "-_3") (pintype "passive"))
      (node (ref "JP3") (pin "3") (pinfunction "-_3") (pintype "passive"))
      (node (ref "JP4") (pin "3") (pinfunction "-_3") (pintype "passive"))
      (node (ref "JP5") (pin "3") (pinfunction "-_3") (pintype "passive"))
      (node (ref "JP6") (pin "3") (pinfunction "-_3") (pintype "passive"))
      (node (ref "R1") (pin "1") (pinfunction "1_1") (pintype "passive"))
      (node (ref "R13") (pin "2") (pinfunction "2_2") (pintype "passive"))
      (node (ref "R14") (pin "1") (pinfunction "1_1") (pintype "passive"))
      (node (ref "R21") (pin "1") (pinfunction "1_1") (pintype "passive"))
      (node (ref "R9") (pin "1") (pinfunction "1_1") (pintype "passive"))
      (node (ref "RF1") (pin "15") (pinfunction "SDN_15") (pintype "input"))
      (node (ref "RF1") (pin "16") (pinfunction "GND_16") (pintype "power_in"))
      (node (ref "RF1") (pin "2") (pinfunction "GND_2") (pintype "power_in"))
      (node (ref "RF1") (pin "9") (pinfunction "GND_9") (pintype "power_in"))
      (node (ref "SKT1") (pin "2") (pinfunction "GND_2") (pintype "passive"))
      (node (ref "U1") (pin "2") (pinfunction "GND_2") (pintype "power_in"))
      (node (ref "U2") (pin "2") (pinfunction "GND_2") (pintype "power_in"))
      (node (ref "U3") (pin "1") (pinfunction "CLKIN_1") (pintype "input"))
      (node (ref "U3") (pin "11") (pinfunction "FSYNC_11") (pintype "passive"))
      (node (ref "U3") (pin "18") (pinfunction "GND_18") (pintype "power_in"))
      (node (ref "U4") (pin "12") (pinfunction "VSSA_12") (pintype "power_in"))
      (node (ref "U4") (pin "18") (pinfunction "VSS_4_18") (pintype "power_in"))
      (node (ref "U4") (pin "28") (pinfunction "PB2/BOOT1_28") (pintype "bidirectional"))
      (node (ref "U4") (pin "63") (pinfunction "VSS_3_63") (pintype "power_in"))
      (node (ref "U5") (pin "3") (pinfunction "GND_3") (pintype "power_in"))
      (node (ref "U6") (pin "11") (pinfunction "GND_11") (pintype "passive"))
      (node (ref "U6") (pin "9") (pinfunction "GND_9") (pintype "passive"))
      (node (ref "U7") (pin "3") (pinfunction "GND_3") (pintype "power_in"))
      (node (ref "U7") (pin "4") (pinfunction "CSB_4") (pintype "passive"))
      (node (ref "U8") (pin "4") (pinfunction "VSS_4") (pintype "power_in"))
      (node (ref "U9") (pin "2") (pinfunction "GND_2") (pintype "power_in"))
      (node (ref "X1") (pin "3") (pinfunction "3_3") (pintype "passive"))
    )
    (net (code "31") (name "Net-(CONN1-Pad3)") (class "Default")
      (node (ref "CONN1") (pin "3") (pinfunction "3_3") (pintype "passive"))
      (node (ref "FIL7") (pin "4") (pinfunction "4_4") (pintype "passive"))
    )
    (net (code "32") (name "Net-(CONN1-Pad4)") (class "Default")
      (node (ref "CONN1") (pin "4") (pinfunction "4_4") (pintype "passive"))
      (node (ref "FIL7") (pin "5") (pinfunction "5_5") (pintype "passive"))
    )
    (net (code "33") (name "Net-(CONN2-Pad3)") (class "Default")
      (node (ref "CONN2") (pin "3") (pinfunction "3_3") (pintype "passive"))
      (node (ref "FIL1") (pin "4") (pinfunction "4_4") (pintype "passive"))
    )
    (net (code "34") (name "Net-(CONN2-Pad4)") (class "Default")
      (node (ref "CONN2") (pin "4") (pinfunction "4_4") (pintype "passive"))
      (node (ref "FIL1") (pin "5") (pinfunction "5_5") (pintype "passive"))
    )
    (net (code "35") (name "Net-(CONN2-Pad5)") (class "Default")
      (node (ref "CONN2") (pin "5") (pinfunction "5_5") (pintype "passive"))
      (node (ref "FIL2") (pin "4") (pinfunction "4_4") (pintype "passive"))
    )
    (net (code "36") (name "Net-(CONN2-Pad6)") (class "Default")
      (node (ref "CONN2") (pin "6") (pinfunction "6_6") (pintype "passive"))
      (node (ref "FIL2") (pin "5") (pinfunction "5_5") (pintype "passive"))
    )
    (net (code "37") (name "Net-(CONN2-Pad7)") (class "Default")
      (node (ref "CONN2") (pin "7") (pinfunction "7_7") (pintype "passive"))
      (node (ref "FIL3") (pin "4") (pinfunction "4_4") (pintype "passive"))
    )
    (net (code "38") (name "Net-(CONN2-Pad8)") (class "Default")
      (node (ref "CONN2") (pin "8") (pinfunction "8_8") (pintype "passive"))
      (node (ref "FIL3") (pin "5") (pinfunction "5_5") (pintype "passive"))
    )
    (net (code "39") (name "Net-(CONN2-Pad9)") (class "Default")
      (node (ref "CONN2") (pin "9") (pinfunction "9_9") (pintype "passive"))
      (node (ref "FIL4") (pin "4") (pinfunction "4_4") (pintype "passive"))
    )
    (net (code "40") (name "Net-(CONN2-Pad10)") (class "Default")
      (node (ref "CONN2") (pin "10") (pinfunction "10_10") (pintype "passive"))
      (node (ref "FIL4") (pin "5") (pinfunction "5_5") (pintype "passive"))
    )
    (net (code "41") (name "Net-(CONN3-Pad3)") (class "Default")
      (node (ref "CONN3") (pin "3") (pinfunction "3_3") (pintype "passive"))
      (node (ref "R7") (pin "2") (pinfunction "2_2") (pintype "passive"))
    )
    (net (code "42") (name "Net-(CONN3-Pad4)") (class "Default")
      (node (ref "CONN3") (pin "4") (pinfunction "4_4") (pintype "passive"))
      (node (ref "R6") (pin "2") (pinfunction "2_2") (pintype "passive"))
    )
    (net (code "43") (name "Net-(CONN4-Pad3)") (class "Default")
      (node (ref "CONN4") (pin "3") (pinfunction "3_3") (pintype "passive"))
      (node (ref "FIL6") (pin "4") (pinfunction "4_4") (pintype "passive"))
    )
    (net (code "44") (name "Net-(CONN4-Pad4)") (class "Default")
      (node (ref "CONN4") (pin "4") (pinfunction "4_4") (pintype "passive"))
      (node (ref "FIL6") (pin "5") (pinfunction "5_5") (pintype "passive"))
    )
    (net (code "45") (name "Net-(D1-COM)") (class "Default")
      (node (ref "D1") (pin "3") (pinfunction "COM_3") (pintype "passive"))
      (node (ref "L4") (pin "2") (pinfunction "2_2") (pintype "passive"))
    )
    (net (code "46") (name "Net-(D2-K)") (class "Default")
      (node (ref "D2") (pin "1") (pinfunction "K_1") (pintype "passive"))
      (node (ref "R1") (pin "2") (pinfunction "2_2") (pintype "passive"))
    )
    (net (code "47") (name "Net-(D3-K)") (class "Default")
      (node (ref "D3") (pin "1") (pinfunction "K_1") (pintype "passive"))
      (node (ref "R5") (pin "1") (pinfunction "1_1") (pintype "passive"))
    )
    (net (code "48") (name "Net-(D4-K)") (class "Default")
      (node (ref "D4") (pin "1") (pinfunction "K_1") (pintype "passive"))
      (node (ref "R20") (pin "1") (pinfunction "1_1") (pintype "passive"))
    )
    (net (code "49") (name "Net-(FIL5-Pad4)") (class "Default")
      (node (ref "FIL5") (pin "4") (pinfunction "4_4") (pintype "passive"))
      (node (ref "R6") (pin "1") (pinfunction "1_1") (pintype "passive"))
    )
    (net (code "50") (name "Net-(FIL5-Pad5)") (class "Default")
      (node (ref "FIL5") (pin "5") (pinfunction "5_5") (pintype "passive"))
      (node (ref "R7") (pin "1") (pinfunction "1_1") (pintype "passive"))
    )
    (net (code "51") (name "Net-(RF1-GPIO_0)") (class "Default")
      (node (ref "RF1") (pin "4") (pinfunction "TX_ANT_4") (pintype "passive"))
      (node (ref "RF1") (pin "6") (pinfunction "GPIO_0_6") (pintype "bidirectional"))
    )
    (net (code "52") (name "Net-(RF1-GPIO_1)") (class "Default")
      (node (ref "RF1") (pin "3") (pinfunction "RX_ANT_3") (pintype "passive"))
      (node (ref "RF1") (pin "7") (pinfunction "GPIO_1_7") (pintype "bidirectional"))
    )
    (net (code "53") (name "Net-(RF1-NIRQ)") (class "Default")
      (node (ref "R19") (pin "1") (pinfunction "1_1") (pintype "passive"))
      (node (ref "RF1") (pin "14") (pinfunction "NIRQ_14") (pintype "output"))
      (node (ref "U4") (pin "54") (pinfunction "PD2_-_Modem_IRQ_54") (pintype "bidirectional"))
    )
    (net (code "54") (name "Net-(RF1-NSEL)") (class "Default")
      (node (ref "R18") (pin "2") (pinfunction "2_2") (pintype "passive"))
      (node (ref "RF1") (pin "13") (pinfunction "NSEL_13") (pintype "input"))
      (node (ref "U4") (pin "50") (pinfunction "PA15_-_SPI3_NSS_50") (pintype "bidirectional"))
    )
    (net (code "55") (name "Net-(RF1-SCK)") (class "Default")
      (node (ref "RF1") (pin "12") (pinfunction "SCK_12") (pintype "input"))
      (node (ref "U4") (pin "51") (pinfunction "PC10_-_SPI3_SCK_51") (pintype "bidirectional"))
      (node (ref "U8") (pin "6") (pinfunction "SCK_6") (pintype "input"))
    )
    (net (code "56") (name "Net-(RF1-SDI)") (class "Default")
      (node (ref "RF1") (pin "11") (pinfunction "SDI_11") (pintype "input"))
      (node (ref "U4") (pin "53") (pinfunction "PC12_-_SPI3_MOSI_53") (pintype "bidirectional"))
      (node (ref "U8") (pin "5") (pinfunction "SI_5") (pintype "input"))
    )
    (net (code "57") (name "Net-(RF1-SDO)") (class "Default")
      (node (ref "RF1") (pin "10") (pinfunction "SDO_10") (pintype "output"))
      (node (ref "U4") (pin "52") (pinfunction "PC11_-_SPI3_MISO_52") (pintype "bidirectional"))
      (node (ref "U8") (pin "2") (pinfunction "SO_2") (pintype "output"))
    )
    (net (code "58") (name "Net-(RF1-VCC)") (class "Default")
      (node (ref "C30") (pin "1") (pinfunction "1_1") (pintype "passive"))
      (node (ref "C31") (pin "1") (pinfunction "1_1") (pintype "passive"))
      (node (ref "RF1") (pin "5") (pinfunction "VCC_5") (pintype "power_in"))
      (node (ref "U9") (pin "5") (pinfunction "VOUT_5") (pintype "power_in"))
    )
    (net (code "59") (name "Net-(U1-BYPASS)") (class "Default")
      (node (ref "C8") (pin "1") (pinfunction "1_1") (pintype "passive"))
      (node (ref "U1") (pin "4") (pinfunction "BYPASS_4") (pintype "passive"))
    )
    (net (code "60") (name "Net-(U2-BYPASS)") (class "Default")
      (node (ref "C9") (pin "1") (pinfunction "1_1") (pintype "passive"))
      (node (ref "U2") (pin "4") (pinfunction "BYPASS_4") (pintype "passive"))
    )
    (net (code "61") (name "Net-(U3-AD0{slash}SDO)") (class "Default")
      (node (ref "U3") (pin "9") (pinfunction "AD0/SDO_9") (pintype "input"))
      (node (ref "U4") (pin "22") (pinfunction "PA6_-_SPI1_MISO_22") (pintype "bidirectional"))
    )
    (net (code "62") (name "Net-(U3-CPOUT)") (class "Default")
      (node (ref "C12") (pin "2") (pinfunction "2_2") (pintype "passive"))
      (node (ref "U3") (pin "20") (pinfunction "CPOUT_20") (pintype "passive"))
    )
    (net (code "63") (name "Net-(U3-INT)") (class "Default")
      (node (ref "U3") (pin "12") (pinfunction "INT_12") (pintype "output"))
      (node (ref "U4") (pin "24") (pinfunction "PC4_-_Gyro_INT_24") (pintype "bidirectional"))
    )
    (net (code "64") (name "Net-(U3-REGOUT)") (class "Default")
      (node (ref "C13") (pin "1") (pinfunction "1_1") (pintype "passive"))
      (node (ref "U3") (pin "10") (pinfunction "REGOUT_10") (pintype "passive"))
    )
    (net (code "65") (name "Net-(U3-SCLK{slash}SCL)") (class "Default")
      (node (ref "U3") (pin "23") (pinfunction "SCLK/SCL_23") (pintype "input"))
      (node (ref "U4") (pin "21") (pinfunction "PA5_-_SPI1_SCK_21") (pintype "bidirectional"))
    )
    (net (code "66") (name "Net-(U3-SDI{slash}SDA)") (class "Default")
      (node (ref "U3") (pin "24") (pinfunction "SDI/SDA_24") (pintype "bidirectional"))
      (node (ref "U4") (pin "23") (pinfunction "PA7_-_SPI1_MOSI_23") (pintype "bidirectional"))
    )
    (net (code "67") (name "Net-(U3-VDD)") (class "Default")
      (node (ref "C10") (pin "2") (pinfunction "2_2") (pintype "passive"))
      (node (ref "C11") (pin "1") (pinfunction "1_1") (pintype "passive"))
      (node (ref "L1") (pin "2") (pinfunction "2_2") (pintype "passive"))
      (node (ref "U3") (pin "13") (pinfunction "VDD_13") (pintype "power_in"))
    )
    (net (code "68") (name "Net-(U3-{slash}CS)") (class "Default")
      (node (ref "R2") (pin "2") (pinfunction "2_2") (pintype "passive"))
      (node (ref "U3") (pin "8") (pinfunction "/CS_8") (pintype "passive"))
      (node (ref "U4") (pin "20") (pinfunction "PA4_-_SPI1_NSS_20") (pintype "bidirectional"))
    )
    (net (code "69") (name "Net-(U4-BOOT0)") (class "Default")
      (node (ref "JP7") (pin "1") (pinfunction "1_1") (pintype "passive"))
      (node (ref "R13") (pin "1") (pinfunction "1_1") (pintype "passive"))
      (node (ref "U4") (pin "60") (pinfunction "BOOT0_60") (pintype "input"))
    )
    (net (code "70") (name "Net-(U4-OSC_IN{slash}PD0)") (class "Default")
      (node (ref "U4") (pin "5") (pinfunction "OSC_IN/PD0_5") (pintype "input"))
      (node (ref "X1") (pin "1") (pinfunction "1_1") (pintype "passive"))
    )
    (net (code "71") (name "Net-(U4-OSC_OUT{slash}PD1)") (class "Default")
      (node (ref "U4") (pin "6") (pinfunction "OSC_OUT/PD1_6") (pintype "output"))
      (node (ref "X1") (pin "2") (pinfunction "2_2") (pintype "passive"))
    )
    (net (code "72") (name "Net-(U4-PB3_-_Flash_CS)") (class "Default")
      (node (ref "R15") (pin "2") (pinfunction "2_2") (pintype "passive"))
      (node (ref "U4") (pin "55") (pinfunction "PB3_-_Flash_CS_55") (pintype "bidirectional"))
      (node (ref "U8") (pin "1") (pinfunction "~{CS}_1") (pintype "input"))
    )
    (net (code "73") (name "Net-(U4-PB7_-_Mag_DRDY)") (class "Default")
      (node (ref "U4") (pin "59") (pinfunction "PB7_-_Mag_DRDY_59") (pintype "bidirectional"))
      (node (ref "U6") (pin "15") (pinfunction "DRDY_15") (pintype "power_in"))
    )
    (net (code "74") (name "Net-(U4-PB8_-_I2C1_SCL)") (class "Default")
      (node (ref "R17") (pin "2") (pinfunction "2_2") (pintype "passive"))
      (node (ref "U4") (pin "61") (pinfunction "PB8_-_I2C1_SCL_61") (pintype "bidirectional"))
      (node (ref "U6") (pin "1") (pinfunction "SCL_1") (pintype "passive"))
      (node (ref "U7") (pin "8") (pinfunction "SCLK_8") (pintype "passive"))
    )
    (net (code "75") (name "Net-(U4-PB9_-_I2C1_SDA)") (class "Default")
      (node (ref "R16") (pin "2") (pinfunction "2_2") (pintype "passive"))
      (node (ref "U4") (pin "62") (pinfunction "PB9_-_I2C1_SDA_62") (pintype "bidirectional"))
      (node (ref "U6") (pin "16") (pinfunction "SDA_16") (pintype "passive"))
      (node (ref "U7") (pin "7") (pinfunction "SDA_7") (pintype "passive"))
    )
    (net (code "76") (name "Net-(U4-PB10-I2C2_SCL)") (class "Default")
      (node (ref "FIL7") (pin "3") (pinfunction "3_3") (pintype "passive"))
      (node (ref "R4") (pin "1") (pinfunction "1_1") (pintype "passive"))
      (node (ref "U4") (pin "29") (pinfunction "PB10-I2C2_SCL_29") (pintype "bidirectional"))
    )
    (net (code "77") (name "Net-(U4-PB11-I2C2_SDA)") (class "Default")
      (node (ref "FIL7") (pin "1") (pinfunction "1_1") (pintype "passive"))
      (node (ref "R3") (pin "1") (pinfunction "1_1") (pintype "passive"))
      (node (ref "U4") (pin "30") (pinfunction "PB11-I2C2_SDA_30") (pintype "bidirectional"))
    )
    (net (code "78") (name "Net-(U4-PB12)") (class "Default")
      (node (ref "FIL1") (pin "3") (pinfunction "3_3") (pintype "passive"))
      (node (ref "U4") (pin "33") (pinfunction "PB12_33") (pintype "bidirectional"))
    )
    (net (code "79") (name "Net-(U4-PB13)") (class "Default")
      (node (ref "FIL1") (pin "1") (pinfunction "1_1") (pintype "passive"))
      (node (ref "U4") (pin "34") (pinfunction "PB13_34") (pintype "bidirectional"))
    )
    (net (code "80") (name "Net-(U4-PC3_-_Frequency)") (class "Default")
      (node (ref "R22") (pin "2") (pinfunction "2_2") (pintype "passive"))
      (node (ref "U4") (pin "11") (pinfunction "PC3_-_Frequency_11") (pintype "bidirectional"))
    )
    (net (code "81") (name "Net-(U4-VCP_1)") (class "Default")
      (node (ref "C14") (pin "2") (pinfunction "2_2") (pintype "passive"))
      (node (ref "U4") (pin "31") (pinfunction "VCP_1_31") (pintype "power_in"))
    )
    (net (code "82") (name "Net-(U4-VCP_2)") (class "Default")
      (node (ref "C25") (pin "2") (pinfunction "2_2") (pintype "passive"))
      (node (ref "U4") (pin "47") (pinfunction "VCP_2_47") (pintype "power_in"))
    )
    (net (code "83") (name "Net-(U5-B)") (class "Default")
      (node (ref "FIL6") (pin "1") (pinfunction "1_1") (pintype "passive"))
      (node (ref "R9") (pin "2") (pinfunction "2_2") (pintype "passive"))
      (node (ref "U5") (pin "2") (pinfunction "B_2") (pintype "input"))
    )
    (net (code "84") (name "Net-(U6-C1)") (class "Default")
      (node (ref "C28") (pin "1") (pinfunction "1_1") (pintype "passive"))
      (node (ref "U6") (pin "10") (pinfunction "C1_10") (pintype "passive"))
    )
    (net (code "85") (name "Net-(U6-SETC)") (class "Default")
      (node (ref "C26") (pin "1") (pinfunction "1_1") (pintype "passive"))
      (node (ref "U6") (pin "12") (pinfunction "SETC_12") (pintype "power_in"))
    )
    (net (code "86") (name "Net-(U6-SETP)") (class "Default")
      (node (ref "C26") (pin "2") (pinfunction "2_2") (pintype "passive"))
      (node (ref "U6") (pin "8") (pinfunction "SETP_8") (pintype "passive"))
    )
    (net (code "87") (name "Net-(U7-PS)") (class "Default")
      (node (ref "C29") (pin "1") (pinfunction "1_1") (pintype "passive"))
      (node (ref "L3") (pin "1") (pinfunction "1_1") (pintype "passive"))
      (node (ref "U7") (pin "1") (pinfunction "VDD_1") (pintype "power_in"))
      (node (ref "U7") (pin "2") (pinfunction "PS_2") (pintype "passive"))
    )
    (net (code "88") (name "Net-(U9-BYPASS)") (class "Default")
      (node (ref "C34") (pin "1") (pinfunction "1_1") (pintype "passive"))
      (node (ref "U9") (pin "4") (pinfunction "BYPASS_4") (pintype "passive"))
    )
    (net (code "89") (name "TO_REGS") (class "Default")
      (node (ref "C2") (pin "1") (pinfunction "1_1") (pintype "passive"))
      (node (ref "C33") (pin "2") (pinfunction "2_2") (pintype "passive"))
      (node (ref "C35") (pin "1") (pinfunction "1_1") (pintype "passive"))
      (node (ref "C36") (pin "1") (pinfunction "1_1") (pintype "passive"))
      (node (ref "C5") (pin "1") (pinfunction "1_1") (pintype "passive"))
      (node (ref "C6") (pin "1") (pinfunction "1_1") (pintype "passive"))
      (node (ref "L4") (pin "1") (pinfunction "1_1") (pintype "passive"))
      (node (ref "U1") (pin "1") (pinfunction "VIN_1") (pintype "power_in"))
      (node (ref "U1") (pin "3") (pinfunction "ON/OFF_3") (pintype "input"))
      (node (ref "U2") (pin "1") (pinfunction "VIN_1") (pintype "power_in"))
      (node (ref "U2") (pin "3") (pinfunction "ON/OFF_3") (pintype "input"))
      (node (ref "U9") (pin "1") (pinfunction "VIN_1") (pintype "power_in"))
      (node (ref "U9") (pin "3") (pinfunction "ON/OFF_3") (pintype "input"))
    )
    (net (code "90") (name "VCC") (class "Default")
      (node (ref "C1") (pin "1") (pinfunction "1_1") (pintype "passive"))
      (node (ref "C15") (pin "1") (pinfunction "1_1") (pintype "passive"))
      (node (ref "C16") (pin "2") (pinfunction "2_2") (pintype "passive"))
      (node (ref "C17") (pin "2") (pinfunction "2_2") (pintype "passive"))
      (node (ref "C18") (pin "1") (pinfunction "1_1") (pintype "passive"))
      (node (ref "C20") (pin "2") (pinfunction "2_2") (pintype "passive"))
      (node (ref "C21") (pin "1") (pinfunction "1_1") (pintype "passive"))
      (node (ref "C22") (pin "2") (pinfunction "2_2") (pintype "passive"))
      (node (ref "C23") (pin "1") (pinfunction "1_1") (pintype "passive"))
      (node (ref "C24") (pin "2") (pinfunction "2_2") (pintype "passive"))
      (node (ref "C27") (pin "1") (pinfunction "1_1") (pintype "passive"))
      (node (ref "C3") (pin "1") (pinfunction "1_1") (pintype "passive"))
      (node (ref "C32") (pin "1") (pinfunction "1_1") (pintype "passive"))
      (node (ref "D2") (pin "2") (pinfunction "A_2") (pintype "passive"))
      (node (ref "D3") (pin "2") (pinfunction "A_2") (pintype "passive"))
      (node (ref "D4") (pin "2") (pinfunction "A_2") (pintype "passive"))
      (node (ref "JP7") (pin "2") (pinfunction "2_2") (pintype "passive"))
      (node (ref "R15") (pin "1") (pinfunction "1_1") (pintype "passive"))
      (node (ref "R16") (pin "1") (pinfunction "1_1") (pintype "passive"))
      (node (ref "R17") (pin "1") (pinfunction "1_1") (pintype "passive"))
      (node (ref "R18") (pin "1") (pinfunction "1_1") (pintype "passive"))
      (node (ref "R19") (pin "2") (pinfunction "2_2") (pintype "passive"))
      (node (ref "R2") (pin "1") (pinfunction "1_1") (pintype "passive"))
      (node (ref "R22") (pin "1") (pinfunction "1_1") (pintype "passive"))
      (node (ref "R3") (pin "2") (pinfunction "2_2") (pintype "passive"))
      (node (ref "R4") (pin "2") (pinfunction "2_2") (pintype "passive"))
      (node (ref "R8") (pin "2") (pinfunction "2_2") (pintype "passive"))
      (node (ref "U1") (pin "5") (pinfunction "VOUT_5") (pintype "power_in"))
      (node (ref "U4") (pin "1") (pinfunction "VBAT_1") (pintype "power_in"))
      (node (ref "U4") (pin "13") (pinfunction "VDDA_13") (pintype "power_in"))
      (node (ref "U4") (pin "19") (pinfunction "VDD_4_19") (pintype "power_in"))
      (node (ref "U4") (pin "32") (pinfunction "VDD_1_32") (pintype "power_in"))
      (node (ref "U4") (pin "48") (pinfunction "VDD_2_48") (pintype "power_in"))
      (node (ref "U4") (pin "64") (pinfunction "VDD_3_64") (pintype "power_in"))
      (node (ref "U5") (pin "5") (pinfunction "VCC_5") (pintype "power_in"))
      (node (ref "U6") (pin "13") (pinfunction "VddIO_13") (pintype "passive"))
      (node (ref "U6") (pin "2") (pinfunction "Vdd_2") (pintype "power_in"))
      (node (ref "U6") (pin "4") (pinfunction "S1_4") (pintype "passive"))
      (node (ref "U8") (pin "3") (pinfunction "~{WP}_3") (pintype "input"))
      (node (ref "U8") (pin "7") (pinfunction "~{HOLD}_7") (pintype "input"))
      (node (ref "U8") (pin "8") (pinfunction "VCC_8") (pintype "power_in"))
    )
    (net (code "91") (name "VCC_ANA") (class "Default")
      (node (ref "C4") (pin "1") (pinfunction "1_1") (pintype "passive"))
      (node (ref "C7") (pin "1") (pinfunction "1_1") (pintype "passive"))
      (node (ref "L1") (pin "1") (pinfunction "1_1") (pintype "passive"))
      (node (ref "L3") (pin "2") (pinfunction "2_2") (pintype "passive"))
      (node (ref "U2") (pin "5") (pinfunction "VOUT_5") (pintype "power_in"))
    )
    (net (code "92") (name "VCC_UNREG") (class "Default")
      (node (ref "CONN1") (pin "2") (pinfunction "2_2") (pintype "passive"))
      (node (ref "CONN2") (pin "2") (pinfunction "2_2") (pintype "passive"))
      (node (ref "CONN3") (pin "2") (pinfunction "2_2") (pintype "passive"))
      (node (ref "CONN4") (pin "2") (pinfunction "2_2") (pintype "passive"))
      (node (ref "D1") (pin "2") (pinfunction "A2_2") (pintype "passive"))
      (node (ref "JP1") (pin "2") (pinfunction "+_2") (pintype "passive"))
      (node (ref "JP2") (pin "2") (pinfunction "+_2") (pintype "passive"))
      (node (ref "JP3") (pin "2") (pinfunction "+_2") (pintype "passive"))
      (node (ref "JP4") (pin "2") (pinfunction "+_2") (pintype "passive"))
      (node (ref "JP5") (pin "2") (pinfunction "+_2") (pintype "passive"))
      (node (ref "JP6") (pin "2") (pinfunction "+_2") (pintype "passive"))
    )
    (net (code "93") (name "unconnected-(CONN5-ID-Pad4)") (class "Default")
      (node (ref "CONN5") (pin "4") (pinfunction "ID_4") (pintype "passive"))
    )
    (net (code "94") (name "unconnected-(RF1-GPIO_2-Pad8)") (class "Default")
      (node (ref "RF1") (pin "8") (pinfunction "GPIO_2_8") (pintype "bidirectional"))
    )
    (net (code "95") (name "unconnected-(RF1-N.C-Pad1)") (class "Default")
      (node (ref "RF1") (pin "1") (pinfunction "N.C_1") (pintype "tri_state"))
    )
    (net (code "96") (name "unconnected-(RF1-N.C-Pad4)") (class "Default")
      (node (ref "RF1") (pin "4") (pinfunction "N.C_4") (pintype "tri_state"))
    )
    (net (code "97") (name "unconnected-(RF1-N.C-Pad8)") (class "Default")
      (node (ref "RF1") (pin "8") (pinfunction "N.C_8") (pintype "tri_state"))
    )
    (net (code "98") (name "unconnected-(RF1-N.C-Pad9)") (class "Default")
      (node (ref "RF1") (pin "9") (pinfunction "N.C_9") (pintype "tri_state"))
    )
    (net (code "99") (name "unconnected-(RF1-N.C-Pad14)") (class "Default")
      (node (ref "RF1") (pin "14") (pinfunction "N.C_14") (pintype "tri_state"))
    )
    (net (code "100") (name "unconnected-(U3-AUX_CL-Pad7)") (class "Default")
      (node (ref "U3") (pin "7") (pinfunction "AUX_CL_7") (pintype "bidirectional"))
    )
    (net (code "101") (name "unconnected-(U3-AUX_DA-Pad6)") (class "Default")
      (node (ref "U3") (pin "6") (pinfunction "AUX_DA_6") (pintype "bidirectional"))
    )
    (net (code "102") (name "unconnected-(U3-CLKOUT-Pad22)") (class "Default")
      (node (ref "U3") (pin "22") (pinfunction "CLKOUT_22") (pintype "output"))
    )
    (net (code "103") (name "unconnected-(U3-NC-Pad2)") (class "Default")
      (node (ref "U3") (pin "2") (pinfunction "NC_2") (pintype "tri_state"))
    )
    (net (code "104") (name "unconnected-(U3-NC-Pad3)") (class "Default")
      (node (ref "U3") (pin "3") (pinfunction "NC_3") (pintype "tri_state"))
    )
    (net (code "105") (name "unconnected-(U3-NC-Pad4)") (class "Default")
      (node (ref "U3") (pin "4") (pinfunction "NC_4") (pintype "tri_state"))
    )
    (net (code "106") (name "unconnected-(U3-NC-Pad5)") (class "Default")
      (node (ref "U3") (pin "5") (pinfunction "NC_5") (pintype "tri_state"))
    )
    (net (code "107") (name "unconnected-(U3-NC-Pad14)") (class "Default")
      (node (ref "U3") (pin "14") (pinfunction "NC_14") (pintype "bidirectional"))
    )
    (net (code "108") (name "unconnected-(U3-NC-Pad15)") (class "Default")
      (node (ref "U3") (pin "15") (pinfunction "NC_15") (pintype "tri_state"))
    )
    (net (code "109") (name "unconnected-(U3-NC-Pad16)") (class "Default")
      (node (ref "U3") (pin "16") (pinfunction "NC_16") (pintype "tri_state"))
    )
    (net (code "110") (name "unconnected-(U3-NC-Pad17)") (class "Default")
      (node (ref "U3") (pin "17") (pinfunction "NC_17") (pintype "tri_state"))
    )
    (net (code "111") (name "unconnected-(U3-RESV-Pad19)") (class "Default")
      (node (ref "U3") (pin "19") (pinfunction "RESV_19") (pintype "passive"))
    )
    (net (code "112") (name "unconnected-(U3-RESV-Pad21)") (class "Default")
      (node (ref "U3") (pin "21") (pinfunction "RESV_21") (pintype "passive"))
    )
    (net (code "113") (name "unconnected-(U4-PB6_--Pad58)") (class "Default")
      (node (ref "U4") (pin "58") (pinfunction "PB6_-_58") (pintype "bidirectional"))
    )
    (net (code "114") (name "unconnected-(U4-PC13_-_RTC-Pad2)") (class "Default")
      (node (ref "U4") (pin "2") (pinfunction "PC13_-_RTC_2") (pintype "bidirectional"))
    )
    (net (code "115") (name "unconnected-(U4-PC14-OSC32_IN-Pad3)") (class "Default")
      (node (ref "U4") (pin "3") (pinfunction "PC14-OSC32_IN_3") (pintype "bidirectional"))
    )
    (net (code "116") (name "unconnected-(U4-PC15-OSC32_OUT-Pad4)") (class "Default")
      (node (ref "U4") (pin "4") (pinfunction "PC15-OSC32_OUT_4") (pintype "bidirectional"))
    )
    (net (code "117") (name "unconnected-(U6-NC-Pad3)") (class "Default")
      (node (ref "U6") (pin "3") (pinfunction "NC_3") (pintype "passive"))
    )
    (net (code "118") (name "unconnected-(U6-NC-Pad5)") (class "Default")
      (node (ref "U6") (pin "5") (pinfunction "NC_5") (pintype "passive"))
    )
    (net (code "119") (name "unconnected-(U6-NC-Pad6)") (class "Default")
      (node (ref "U6") (pin "6") (pinfunction "NC_6") (pintype "passive"))
    )
    (net (code "120") (name "unconnected-(U6-NC-Pad7)") (class "Default")
      (node (ref "U6") (pin "7") (pinfunction "NC_7") (pintype "passive"))
    )
    (net (code "121") (name "unconnected-(U6-NC-Pad8)") (class "Default")
      (node (ref "U6") (pin "8") (pinfunction "NC_8") (pintype "passive"))
    )
    (net (code "122") (name "unconnected-(U6-NC-Pad14)") (class "Default")
      (node (ref "U6") (pin "14") (pinfunction "NC_14") (pintype "passive"))
    )
    (net (code "123") (name "unconnected-(U7-CSB-Pad5)") (class "Default")
      (node (ref "U7") (pin "5") (pinfunction "CSB_5") (pintype "passive"))
    )
    (net (code "124") (name "unconnected-(U7-SDO-Pad6)") (class "Default")
      (node (ref "U7") (pin "6") (pinfunction "SDO_6") (pintype "passive"))
    )
  )
)
